# LCmeter0-nokia3310.net
KiCad netlist of a schematic drawn in EAGLE
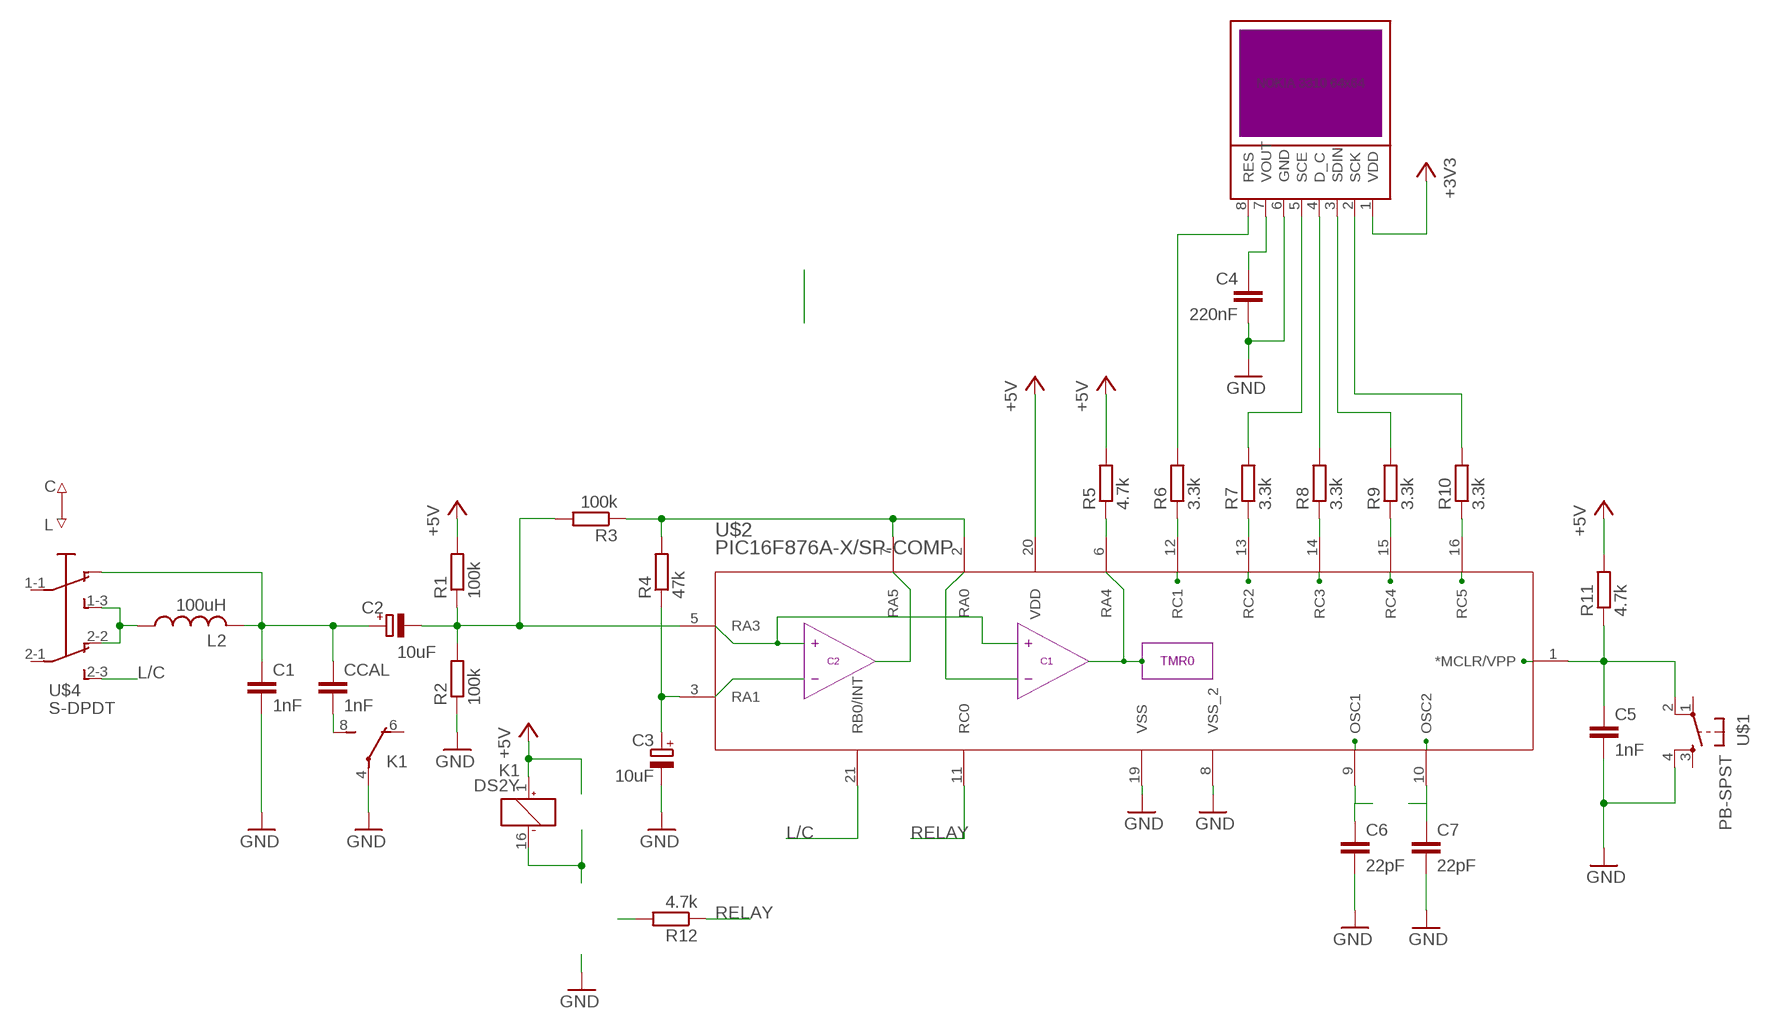
[diagram p0: schematic, sheet 1]

(export (version "E")
  (design (tool "Eeschema 10.0.6"))
  (components
    (comp (ref "C1")
      (value "1nF")
      (footprint "eagle-import:C050-025X075")
      (libsource (lib "eagle-import") (part "C-EU050-025X075"))
    )
    (comp (ref "C2")
      (value "10uF")
      (footprint "eagle-import:E2,5-5")
      (libsource (lib "eagle-import") (part "CPOL-EUE2.5-5"))
    )
    (comp (ref "C3")
      (value "10uF")
      (footprint "eagle-import:E2,5-5")
      (libsource (lib "eagle-import") (part "CPOL-EUE2.5-5"))
    )
    (comp (ref "C4")
      (value "220nF")
      (footprint "eagle-import:C050-025X075")
      (libsource (lib "eagle-import") (part "C-EU050-025X075"))
    )
    (comp (ref "C5")
      (value "1nF")
      (footprint "eagle-import:C050-025X075")
      (libsource (lib "eagle-import") (part "C-EU050-025X075"))
    )
    (comp (ref "C6")
      (value "22pF")
      (footprint "eagle-import:C050-025X075")
      (libsource (lib "eagle-import") (part "C-EU050-025X075"))
    )
    (comp (ref "C7")
      (value "22pF")
      (footprint "eagle-import:C050-025X075")
      (libsource (lib "eagle-import") (part "C-EU050-025X075"))
    )
    (comp (ref "CCAL")
      (value "1nF")
      (footprint "eagle-import:C050-025X075")
      (libsource (lib "eagle-import") (part "C-EU050-025X075"))
    )
    (comp (ref "K1")
      (value "DS2Y")
      (footprint "eagle-import:DS2Y")
      (fields (field (name "MPN") "DS2Y-S-DC5V"))
      (libsource (lib "eagle-import") (part "DS2Y-S-DC5V"))
    )
    (comp (ref "L2")
      (value "100uH")
      (footprint "eagle-import:IR-2")
      (libsource (lib "eagle-import") (part "L-USIR-2"))
    )
    (comp (ref "R1")
      (value "100k")
      (footprint "eagle-import:0204_7")
      (libsource (lib "eagle-import") (part "R-EU_0204/7"))
    )
    (comp (ref "R2")
      (value "100k")
      (footprint "eagle-import:0204V")
      (libsource (lib "eagle-import") (part "R-EU_0204/2V"))
    )
    (comp (ref "R3")
      (value "100k")
      (footprint "eagle-import:0204_7")
      (libsource (lib "eagle-import") (part "R-EU_0204/7"))
    )
    (comp (ref "R4")
      (value "47k")
      (footprint "eagle-import:0204V")
      (libsource (lib "eagle-import") (part "R-EU_0204/2V"))
    )
    (comp (ref "R5")
      (value "4.7k")
      (footprint "eagle-import:0204_7")
      (libsource (lib "eagle-import") (part "R-EU_0204/7"))
    )
    (comp (ref "R6")
      (value "3.3k")
      (footprint "eagle-import:0207_10")
      (libsource (lib "eagle-import") (part "R-EU_0207/10"))
    )
    (comp (ref "R7")
      (value "3.3k")
      (footprint "eagle-import:0207_10")
      (libsource (lib "eagle-import") (part "R-EU_0207/10"))
    )
    (comp (ref "R8")
      (value "3.3k")
      (footprint "eagle-import:0207_10")
      (libsource (lib "eagle-import") (part "R-EU_0207/10"))
    )
    (comp (ref "R9")
      (value "3.3k")
      (footprint "eagle-import:0207_10")
      (libsource (lib "eagle-import") (part "R-EU_0207/10"))
    )
    (comp (ref "R10")
      (value "3.3k")
      (footprint "eagle-import:0207_10")
      (libsource (lib "eagle-import") (part "R-EU_0207/10"))
    )
    (comp (ref "R11")
      (value "4.7k")
      (footprint "eagle-import:0204V")
      (libsource (lib "eagle-import") (part "R-EU_0204/2V"))
    )
    (comp (ref "R12")
      (value "4.7k")
      (footprint "eagle-import:0204_7")
      (libsource (lib "eagle-import") (part "R-EU_0204/7"))
    )
    (comp (ref "U$1")
      (value "PB-SPST")
      (footprint "eagle-import:PB-5")
      (libsource (lib "eagle-import") (part "PB-SPST"))
    )
    (comp (ref "U$2")
      (value "PIC16F876A-X/SP-COMP")
      (footprint "eagle-import:DIL28-3")
      (libsource (lib "eagle-import") (part "PIC16F876A-X/SP-COMP"))
    )
    (comp (ref "U$3")
      (value "NOKIA-3310-64X64")
      (footprint "eagle-import:1X8")
      (libsource (lib "eagle-import") (part "NOKIA-3310-64X64"))
    )
    (comp (ref "U$4")
      (value "S-DPDT")
      (footprint "eagle-import:DPDT")
      (libsource (lib "eagle-import") (part "S-DPDT"))
    )
  )
  (nets
    (net (code "1") (name "+3V3") (class "Default")
      (node (ref "U$3") (pin "1") (pinfunction "VDD_1") (pintype "passive"))
    )
    (net (code "2") (name "+5V") (class "Default")
      (node (ref "K1") (pin "1") (pinfunction "+_1") (pintype "passive"))
      (node (ref "R1") (pin "2") (pinfunction "2_2") (pintype "passive"))
      (node (ref "R11") (pin "2") (pinfunction "2_2") (pintype "passive"))
      (node (ref "R5") (pin "2") (pinfunction "2_2") (pintype "passive"))
      (node (ref "U$2") (pin "20") (pinfunction "VDD_20") (pintype "passive"))
    )
    (net (code "3") (name "/L{slash}C") (class "Default")
      (node (ref "U$2") (pin "21") (pinfunction "RB0/INT_21") (pintype "passive"))
      (node (ref "U$4") (pin "2-3") (pinfunction "2-3_2-3") (pintype "passive"))
    )
    (net (code "4") (name "/RELAY") (class "Default")
      (node (ref "R12") (pin "1") (pinfunction "1_1") (pintype "passive"))
      (node (ref "U$2") (pin "11") (pinfunction "RC0_11") (pintype "passive"))
    )
    (net (code "5") (name "GND") (class "Default")
      (node (ref "C1") (pin "2") (pinfunction "2_2") (pintype "passive"))
      (node (ref "C3") (pin "-") (pinfunction "-_-") (pintype "passive"))
      (node (ref "C4") (pin "2") (pinfunction "2_2") (pintype "passive"))
      (node (ref "C5") (pin "2") (pinfunction "2_2") (pintype "passive"))
      (node (ref "C6") (pin "2") (pinfunction "2_2") (pintype "passive"))
      (node (ref "C7") (pin "2") (pinfunction "2_2") (pintype "passive"))
      (node (ref "K1") (pin "4") (pinfunction "P_4") (pintype "passive"))
      (node (ref "R2") (pin "1") (pinfunction "1_1") (pintype "passive"))
      (node (ref "U$1") (pin "4") (pinfunction "S1_4") (pintype "passive"))
      (node (ref "U$2") (pin "19") (pinfunction "VSS_19") (pintype "passive"))
      (node (ref "U$2") (pin "8") (pinfunction "VSS_2_8") (pintype "passive"))
      (node (ref "U$3") (pin "6") (pinfunction "GND_6") (pintype "passive"))
    )
    (net (code "6") (name "Net-(C1-Pad1)") (class "Default")
      (node (ref "C1") (pin "1") (pinfunction "1_1") (pintype "passive"))
      (node (ref "C2") (pin "+") (pinfunction "+_+") (pintype "passive"))
      (node (ref "CCAL") (pin "1") (pinfunction "1_1") (pintype "passive"))
      (node (ref "L2") (pin "2") (pinfunction "2_2") (pintype "passive"))
      (node (ref "U$4") (pin "1-2") (pinfunction "1-2_1-2") (pintype "passive"))
    )
    (net (code "7") (name "Net-(K1B-S)") (class "Default")
      (node (ref "CCAL") (pin "2") (pinfunction "2_2") (pintype "passive"))
      (node (ref "K1") (pin "8") (pinfunction "S_8") (pintype "passive"))
    )
    (net (code "8") (name "Net-(L2-Pad1)") (class "Default")
      (node (ref "L2") (pin "1") (pinfunction "1_1") (pintype "passive"))
      (node (ref "U$4") (pin "1-3") (pinfunction "1-3_1-3") (pintype "passive"))
      (node (ref "U$4") (pin "2-2") (pinfunction "2-2_2-2") (pintype "passive"))
    )
    (net (code "9") (name "Net-(U$1-P1)") (class "Default")
      (node (ref "C5") (pin "1") (pinfunction "1_1") (pintype "passive"))
      (node (ref "R11") (pin "1") (pinfunction "1_1") (pintype "passive"))
      (node (ref "U$1") (pin "2") (pinfunction "P1_2") (pintype "passive"))
      (node (ref "U$2") (pin "1") (pinfunction "*MCLR/VPP_1") (pintype "passive"))
    )
    (net (code "10") (name "Net-(U$2-OSC1)") (class "Default")
      (node (ref "C6") (pin "1") (pinfunction "1_1") (pintype "passive"))
      (node (ref "U$2") (pin "9") (pinfunction "OSC1_9") (pintype "passive"))
    )
    (net (code "11") (name "Net-(U$2-OSC2)") (class "Default")
      (node (ref "C7") (pin "1") (pinfunction "1_1") (pintype "passive"))
      (node (ref "U$2") (pin "10") (pinfunction "OSC2_10") (pintype "passive"))
    )
    (net (code "12") (name "Net-(U$2-RA0)") (class "Default")
      (node (ref "R3") (pin "1") (pinfunction "1_1") (pintype "passive"))
      (node (ref "R4") (pin "2") (pinfunction "2_2") (pintype "passive"))
      (node (ref "U$2") (pin "2") (pinfunction "RA0_2") (pintype "passive"))
      (node (ref "U$2") (pin "7") (pinfunction "RA5_7") (pintype "passive"))
    )
    (net (code "13") (name "Net-(U$2-RA1)") (class "Default")
      (node (ref "C3") (pin "+") (pinfunction "+_+") (pintype "passive"))
      (node (ref "R4") (pin "1") (pinfunction "1_1") (pintype "passive"))
      (node (ref "U$2") (pin "3") (pinfunction "RA1_3") (pintype "passive"))
    )
    (net (code "14") (name "Net-(U$2-RA3)") (class "Default")
      (node (ref "C2") (pin "-") (pinfunction "-_-") (pintype "passive"))
      (node (ref "R1") (pin "1") (pinfunction "1_1") (pintype "passive"))
      (node (ref "R2") (pin "2") (pinfunction "2_2") (pintype "passive"))
      (node (ref "R3") (pin "2") (pinfunction "2_2") (pintype "passive"))
      (node (ref "U$2") (pin "5") (pinfunction "RA3_5") (pintype "passive"))
    )
    (net (code "15") (name "Net-(U$2-RA4)") (class "Default")
      (node (ref "R5") (pin "1") (pinfunction "1_1") (pintype "passive"))
      (node (ref "U$2") (pin "6") (pinfunction "RA4_6") (pintype "passive"))
    )
    (net (code "16") (name "Net-(U$2-RC1)") (class "Default")
      (node (ref "R6") (pin "1") (pinfunction "1_1") (pintype "passive"))
      (node (ref "U$2") (pin "12") (pinfunction "RC1_12") (pintype "passive"))
    )
    (net (code "17") (name "Net-(U$2-RC2)") (class "Default")
      (node (ref "R7") (pin "1") (pinfunction "1_1") (pintype "passive"))
      (node (ref "U$2") (pin "13") (pinfunction "RC2_13") (pintype "passive"))
    )
    (net (code "18") (name "Net-(U$2-RC3)") (class "Default")
      (node (ref "R8") (pin "1") (pinfunction "1_1") (pintype "passive"))
      (node (ref "U$2") (pin "14") (pinfunction "RC3_14") (pintype "passive"))
    )
    (net (code "19") (name "Net-(U$2-RC4)") (class "Default")
      (node (ref "R9") (pin "1") (pinfunction "1_1") (pintype "passive"))
      (node (ref "U$2") (pin "15") (pinfunction "RC4_15") (pintype "passive"))
    )
    (net (code "20") (name "Net-(U$2-RC5)") (class "Default")
      (node (ref "R10") (pin "1") (pinfunction "1_1") (pintype "passive"))
      (node (ref "U$2") (pin "16") (pinfunction "RC5_16") (pintype "passive"))
    )
    (net (code "21") (name "Net-(U$3-D_C)") (class "Default")
      (node (ref "R8") (pin "2") (pinfunction "2_2") (pintype "passive"))
      (node (ref "U$3") (pin "4") (pinfunction "D_C_4") (pintype "passive"))
    )
    (net (code "22") (name "Net-(U$3-RES)") (class "Default")
      (node (ref "R6") (pin "2") (pinfunction "2_2") (pintype "passive"))
      (node (ref "U$3") (pin "8") (pinfunction "RES_8") (pintype "passive"))
    )
    (net (code "23") (name "Net-(U$3-SCE)") (class "Default")
      (node (ref "R7") (pin "2") (pinfunction "2_2") (pintype "passive"))
      (node (ref "U$3") (pin "5") (pinfunction "SCE_5") (pintype "passive"))
    )
    (net (code "24") (name "Net-(U$3-SCK)") (class "Default")
      (node (ref "R10") (pin "2") (pinfunction "2_2") (pintype "passive"))
      (node (ref "U$3") (pin "2") (pinfunction "SCK_2") (pintype "passive"))
    )
    (net (code "25") (name "Net-(U$3-SDIN)") (class "Default")
      (node (ref "R9") (pin "2") (pinfunction "2_2") (pintype "passive"))
      (node (ref "U$3") (pin "3") (pinfunction "SDIN_3") (pintype "passive"))
    )
    (net (code "26") (name "Net-(U$3-VOUT)") (class "Default")
      (node (ref "C4") (pin "1") (pinfunction "1_1") (pintype "passive"))
      (node (ref "U$3") (pin "7") (pinfunction "VOUT_7") (pintype "passive"))
    )
    (net (code "27") (name "unconnected-(K1A---Pad16)") (class "Default")
      (node (ref "K1") (pin "16") (pinfunction "-_16") (pintype "passive"))
    )
    (net (code "28") (name "unconnected-(K1B-O-Pad6)") (class "Default")
      (node (ref "K1") (pin "6") (pinfunction "O_6") (pintype "passive"))
    )
    (net (code "29") (name "unconnected-(R12-Pad2)") (class "Default")
      (node (ref "R12") (pin "2") (pinfunction "2_2") (pintype "passive"))
    )
    (net (code "30") (name "unconnected-(U$1-P-Pad1)") (class "Default")
      (node (ref "U$1") (pin "1") (pinfunction "P_1") (pintype "passive"))
    )
    (net (code "31") (name "unconnected-(U$1-S-Pad3)") (class "Default")
      (node (ref "U$1") (pin "3") (pinfunction "S_3") (pintype "passive"))
    )
    (net (code "32") (name "unconnected-(U$4-Pad1-1)") (class "Default")
      (node (ref "U$4") (pin "1-1") (pinfunction "1-1_1-1") (pintype "passive"))
    )
    (net (code "33") (name "unconnected-(U$4-Pad2-1)") (class "Default")
      (node (ref "U$4") (pin "2-1") (pinfunction "2-1_2-1") (pintype "passive"))
    )
  )
)
